# top.net
KiCad netlist of a schematic drawn in Altium Designer
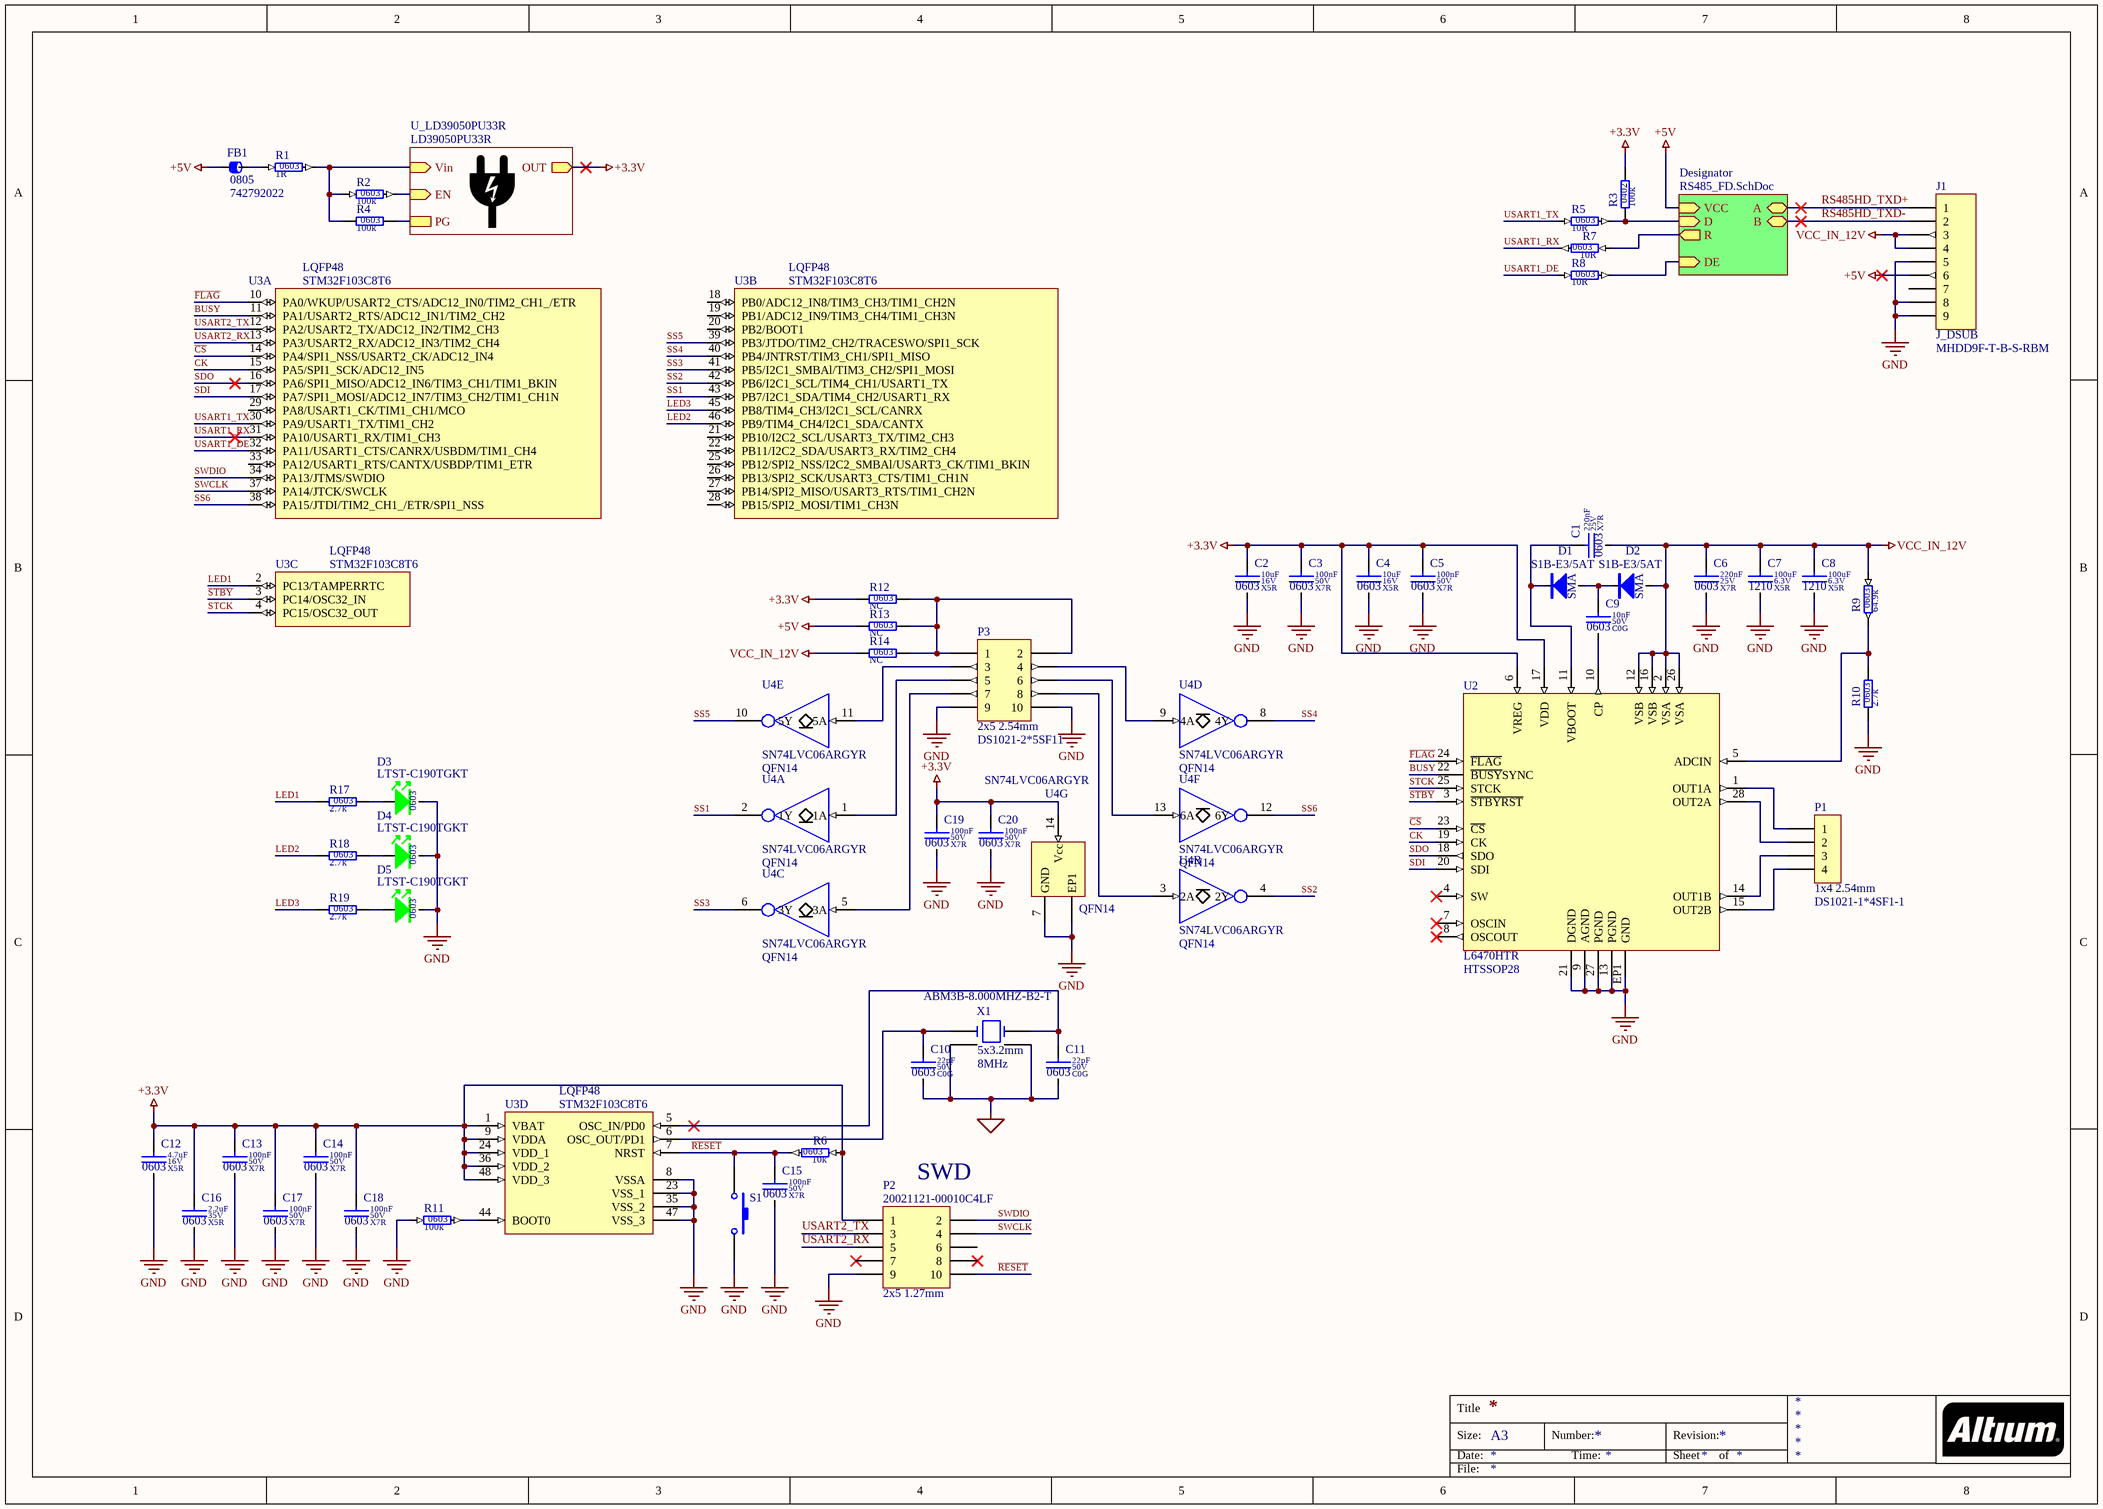
[diagram p0: top.SchDoc]

(export (version "E")
  (design (tool "Eeschema 10.0.6"))
  (components
    (comp (ref "C1")
      (value "220nF")
      (footprint "C_0603_1608")
      (description "Capacitor")
      (fields
        (field (name "DIELECTRIC") "X7R")
        (field (name "VOLTAGE") "25V")
        (field (name "SCH_FOOTPRINT") "0603")
        (field (name "PART NUMBER") "C_220nF_25V_X7R_0603_10")
        (field (name "MANUFACTURER") "Murata")
      )
      (libsource (lib "Library") (part "C"))
    )
    (comp (ref "C2")
      (value "10uF")
      (footprint "C_0603_1608")
      (description "Capacitor")
      (fields
        (field (name "DIELECTRIC") "X5R")
        (field (name "VOLTAGE") "16V")
        (field (name "SCH_FOOTPRINT") "0603")
        (field (name "PART NUMBER") "C_10uF_16V_X5R_0603_20")
        (field (name "MANUFACTURER") "Samsung Electro-Mechanics")
      )
      (libsource (lib "Library") (part "C"))
    )
    (comp (ref "C3")
      (value "100nF")
      (footprint "C_0603_1608")
      (description "Capacitor")
      (fields
        (field (name "DIELECTRIC") "X7R")
        (field (name "VOLTAGE") "50V")
        (field (name "SCH_FOOTPRINT") "0603")
        (field (name "PART NUMBER") "C_100nF_50V_X7R_0603_5")
        (field (name "MANUFACTURER") "Samsung")
      )
      (libsource (lib "Library") (part "C"))
    )
    (comp (ref "C4")
      (value "10uF")
      (footprint "C_0603_1608")
      (description "Capacitor")
      (fields
        (field (name "DIELECTRIC") "X5R")
        (field (name "VOLTAGE") "16V")
        (field (name "SCH_FOOTPRINT") "0603")
        (field (name "PART NUMBER") "C_10uF_16V_X5R_0603_20")
        (field (name "MANUFACTURER") "Samsung Electro-Mechanics")
      )
      (libsource (lib "Library") (part "C"))
    )
    (comp (ref "C5")
      (value "100nF")
      (footprint "C_0603_1608")
      (description "Capacitor")
      (fields
        (field (name "DIELECTRIC") "X7R")
        (field (name "VOLTAGE") "50V")
        (field (name "SCH_FOOTPRINT") "0603")
        (field (name "PART NUMBER") "C_100nF_50V_X7R_0603_5")
        (field (name "MANUFACTURER") "Samsung")
      )
      (libsource (lib "Library") (part "C"))
    )
    (comp (ref "C6")
      (value "220nF")
      (footprint "C_0603_1608")
      (description "Capacitor")
      (fields
        (field (name "DIELECTRIC") "X7R")
        (field (name "VOLTAGE") "25V")
        (field (name "SCH_FOOTPRINT") "0603")
        (field (name "PART NUMBER") "C_220nF_25V_X7R_0603_10")
        (field (name "MANUFACTURER") "Murata")
      )
      (libsource (lib "Library") (part "C"))
    )
    (comp (ref "C7")
      (value "100uF")
      (footprint "C_1210_3225")
      (description "Capacitor")
      (fields
        (field (name "DIELECTRIC") "X5R")
        (field (name "VOLTAGE") "6.3V")
        (field (name "SCH_FOOTPRINT") "1210")
        (field (name "PART NUMBER") "C_100uF_6.3V_X5R_1210_20")
        (field (name "MANUFACTURER") "TDK")
      )
      (libsource (lib "Library") (part "C"))
    )
    (comp (ref "C8")
      (value "100uF")
      (footprint "C_1210_3225")
      (description "Capacitor")
      (fields
        (field (name "DIELECTRIC") "X5R")
        (field (name "VOLTAGE") "6.3V")
        (field (name "SCH_FOOTPRINT") "1210")
        (field (name "PART NUMBER") "C_100uF_6.3V_X5R_1210_20")
        (field (name "MANUFACTURER") "TDK")
      )
      (libsource (lib "Library") (part "C"))
    )
    (comp (ref "C9")
      (value "10nF")
      (footprint "C_0603_1608")
      (description "Capacitor")
      (fields
        (field (name "DIELECTRIC") "C0G")
        (field (name "VOLTAGE") "50V")
        (field (name "SCH_FOOTPRINT") "0603")
        (field (name "PART NUMBER") "C_10nF_50V_C0G_0603_5")
        (field (name "MANUFACTURER") "Murata")
      )
      (libsource (lib "") (part "C_1"))
    )
    (comp (ref "C10")
      (value "22pF")
      (footprint "C_0603_1608")
      (description "Capacitor")
      (fields
        (field (name "DIELECTRIC") "C0G")
        (field (name "VOLTAGE") "50V")
        (field (name "SCH_FOOTPRINT") "0603")
        (field (name "PART NUMBER") "C_22pF_50V_C0G_0603_5")
        (field (name "MANUFACTURER") "AVX")
      )
      (libsource (lib "Library") (part "C"))
    )
    (comp (ref "C11")
      (value "22pF")
      (footprint "C_0603_1608")
      (description "Capacitor")
      (fields
        (field (name "DIELECTRIC") "C0G")
        (field (name "VOLTAGE") "50V")
        (field (name "SCH_FOOTPRINT") "0603")
        (field (name "PART NUMBER") "C_22pF_50V_C0G_0603_5")
        (field (name "MANUFACTURER") "AVX")
      )
      (libsource (lib "Library") (part "C"))
    )
    (comp (ref "C12")
      (value "4.7uF")
      (footprint "C_0603_1608")
      (description "Capacitor")
      (fields
        (field (name "DIELECTRIC") "X5R")
        (field (name "VOLTAGE") "16V")
        (field (name "SCH_FOOTPRINT") "0603")
        (field (name "PART NUMBER") "C_4.7uF_16V_X5R_0603_10")
        (field (name "MANUFACTURER") "Murata")
      )
      (libsource (lib "Library") (part "C"))
    )
    (comp (ref "C13")
      (value "100nF")
      (footprint "C_0603_1608")
      (description "Capacitor")
      (fields
        (field (name "DIELECTRIC") "X7R")
        (field (name "VOLTAGE") "50V")
        (field (name "SCH_FOOTPRINT") "0603")
        (field (name "PART NUMBER") "C_100nF_50V_X7R_0603_5")
        (field (name "MANUFACTURER") "Samsung")
      )
      (libsource (lib "Library") (part "C"))
    )
    (comp (ref "C14")
      (value "100nF")
      (footprint "C_0603_1608")
      (description "Capacitor")
      (fields
        (field (name "DIELECTRIC") "X7R")
        (field (name "VOLTAGE") "50V")
        (field (name "SCH_FOOTPRINT") "0603")
        (field (name "PART NUMBER") "C_100nF_50V_X7R_0603_5")
        (field (name "MANUFACTURER") "Samsung")
      )
      (libsource (lib "Library") (part "C"))
    )
    (comp (ref "C15")
      (value "100nF")
      (footprint "C_0603_1608")
      (description "Capacitor")
      (fields
        (field (name "DIELECTRIC") "X7R")
        (field (name "VOLTAGE") "50V")
        (field (name "SCH_FOOTPRINT") "0603")
        (field (name "PART NUMBER") "C_100nF_50V_X7R_0603_5")
        (field (name "MANUFACTURER") "Samsung")
      )
      (libsource (lib "Library") (part "C"))
    )
    (comp (ref "C16")
      (value "2.2uF")
      (footprint "C_0603_1608")
      (description "Capacitor")
      (fields
        (field (name "DIELECTRIC") "X5R")
        (field (name "VOLTAGE") "35V")
        (field (name "SCH_FOOTPRINT") "0603")
        (field (name "PART NUMBER") "C_2.2uF_35V_X5R_0603_10")
        (field (name "MANUFACTURER") "Murata")
      )
      (libsource (lib "Library") (part "C"))
    )
    (comp (ref "C17")
      (value "100nF")
      (footprint "C_0603_1608")
      (description "Capacitor")
      (fields
        (field (name "DIELECTRIC") "X7R")
        (field (name "VOLTAGE") "50V")
        (field (name "SCH_FOOTPRINT") "0603")
        (field (name "PART NUMBER") "C_100nF_50V_X7R_0603_5")
        (field (name "MANUFACTURER") "Samsung")
      )
      (libsource (lib "Library") (part "C"))
    )
    (comp (ref "C18")
      (value "100nF")
      (footprint "C_0603_1608")
      (description "Capacitor")
      (fields
        (field (name "DIELECTRIC") "X7R")
        (field (name "VOLTAGE") "50V")
        (field (name "SCH_FOOTPRINT") "0603")
        (field (name "PART NUMBER") "C_100nF_50V_X7R_0603_5")
        (field (name "MANUFACTURER") "Samsung")
      )
      (libsource (lib "Library") (part "C"))
    )
    (comp (ref "C19")
      (value "100nF")
      (footprint "C_0603_1608")
      (description "Capacitor")
      (fields
        (field (name "DIELECTRIC") "X7R")
        (field (name "VOLTAGE") "50V")
        (field (name "SCH_FOOTPRINT") "0603")
        (field (name "PART NUMBER") "C_100nF_50V_X7R_0603_5")
        (field (name "MANUFACTURER") "Samsung")
      )
      (libsource (lib "Library") (part "C"))
    )
    (comp (ref "C20")
      (value "100nF")
      (footprint "C_0603_1608")
      (description "Capacitor")
      (fields
        (field (name "DIELECTRIC") "X7R")
        (field (name "VOLTAGE") "50V")
        (field (name "SCH_FOOTPRINT") "0603")
        (field (name "PART NUMBER") "C_100nF_50V_X7R_0603_5")
        (field (name "MANUFACTURER") "Samsung")
      )
      (libsource (lib "Library") (part "C"))
    )
    (comp (ref "D1")
      (value "S1B-E3/5AT")
      (footprint "SMA_DO-214AC")
      (fields
        (field (name "SCH_FOOTPRINT") "SMA")
        (field (name "PART NUMBER") "D_S1BE3/61T_1A_100V_SMA")
        (field (name "VOLTAGE") "100V")
        (field (name "MANUFACTURER") "Vishay")
      )
      (libsource (lib "Library") (part "D"))
    )
    (comp (ref "D2")
      (value "S1B-E3/5AT")
      (footprint "SMA_DO-214AC")
      (fields
        (field (name "SCH_FOOTPRINT") "SMA")
        (field (name "PART NUMBER") "D_S1BE3/61T_1A_100V_SMA")
        (field (name "VOLTAGE") "100V")
        (field (name "MANUFACTURER") "Vishay")
      )
      (libsource (lib "Library") (part "D"))
    )
    (comp (ref "D3")
      (value "LTST-C190TGKT")
      (footprint "OL_0603_1608")
      (description "LED GREEN")
      (fields
        (field (name "SCH_FOOTPRINT") "0603")
        (field (name "PART NUMBER") "OL_G_0603")
        (field (name "MANUFACTURER") "Lite-On")
      )
      (libsource (lib "Library") (part "OL_G"))
    )
    (comp (ref "D4")
      (value "LTST-C190TGKT")
      (footprint "OL_0603_1608")
      (description "LED GREEN")
      (fields
        (field (name "SCH_FOOTPRINT") "0603")
        (field (name "PART NUMBER") "OL_G_0603")
        (field (name "MANUFACTURER") "Lite-On")
      )
      (libsource (lib "Library") (part "OL_G"))
    )
    (comp (ref "D5")
      (value "LTST-C190TGKT")
      (footprint "OL_0603_1608")
      (description "LED GREEN")
      (fields
        (field (name "SCH_FOOTPRINT") "0603")
        (field (name "PART NUMBER") "OL_G_0603")
        (field (name "MANUFACTURER") "Lite-On")
      )
      (libsource (lib "Library") (part "OL_G"))
    )
    (comp (ref "FB1")
      (value "742792022")
      (footprint "FB_0805_2012")
      (description "Ferrite Bead")
      (fields
        (field (name "PART NUMBER") "FB_742792022")
        (field (name "SCH_FOOTPRINT") "0805")
        (field (name "MANUFACTURER") "Wurth")
      )
      (libsource (lib "Library") (part "FB"))
    )
    (comp (ref "J1")
      (value "MHDD9F-T-B-S-RBM")
      (footprint "J_DSUB_MHDD9F-T-B-S-RBM")
      (description "Header, 9-Pin")
      (fields
        (field (name "SCH_FOOTPRINT") "J_DSUB")
        (field (name "PART NUMBER") "J_DSUB")
        (field (name "Comment") "DSUB 9 Pin")
      )
      (libsource (lib "Library") (part "J_DSUB"))
    )
    (comp (ref "P1")
      (value "DS1021-1*4SF1-1")
      (footprint "P_HEADER_1x4_2.54")
      (description "Pin Header")
      (fields
        (field (name "SCH_FOOTPRINT") "1x4 2.54mm")
        (field (name "PART NUMBER") "P_HEADER_1x4_2.54")
        (field (name "MANUFACTURER") "Connfly")
      )
      (libsource (lib "Library") (part "P_HEADER_1x4"))
    )
    (comp (ref "P2")
      (value "20021121-00010C4LF")
      (footprint "P_HEADER_2x5_1.27")
      (description "Header, 10-Pin, Dual row")
      (fields
        (field (name "PART NUMBER") "P_HEADER_2x5_1.27")
        (field (name "SCH_FOOTPRINT") "2x5 1.27mm")
        (field (name "MANUFACTURER") "FCI")
      )
      (libsource (lib "Library") (part "P_HEADER_2x5"))
    )
    (comp (ref "P3")
      (value "DS1021-2*5SF11")
      (footprint "P_HEADER_2x5_2.54")
      (description "Pin Header")
      (fields
        (field (name "SCH_FOOTPRINT") "2x5 2.54mm")
        (field (name "PART NUMBER") "P_HEADER_2x5_2.54")
        (field (name "MANUFACTURER") "Connfly")
      )
      (libsource (lib "") (part "P_HEADER_2x5_1"))
    )
    (comp (ref "R1")
      (value "1R")
      (footprint "R_0603_1608")
      (fields
        (field (name "SCH_FOOTPRINT") "0603")
        (field (name "PART NUMBER") "R_1R_0603_1")
        (field (name "VOLTAGE") "50V")
        (field (name "POWER") "100mW")
      )
      (libsource (lib "Library") (part "R"))
    )
    (comp (ref "R2")
      (value "100k")
      (footprint "R_0603_1608")
      (fields
        (field (name "SCH_FOOTPRINT") "0603")
        (field (name "PART NUMBER") "R_100k_0603_1")
        (field (name "VOLTAGE") "50V")
        (field (name "POWER") "100mW")
      )
      (libsource (lib "Library") (part "R"))
    )
    (comp (ref "R3")
      (value "100k")
      (footprint "R_0402_1005")
      (fields
        (field (name "SCH_FOOTPRINT") "0402")
        (field (name "PART NUMBER") "R_100k_0402_1")
        (field (name "VOLTAGE") "50V")
        (field (name "POWER") "63mW")
      )
      (libsource (lib "") (part "R_2"))
    )
    (comp (ref "R4")
      (value "100k")
      (footprint "R_0603_1608")
      (fields
        (field (name "SCH_FOOTPRINT") "0603")
        (field (name "PART NUMBER") "R_100k_0603_1")
        (field (name "VOLTAGE") "50V")
        (field (name "POWER") "100mW")
      )
      (libsource (lib "") (part "R_2"))
    )
    (comp (ref "R5")
      (value "10R")
      (footprint "R_0603_1608")
      (fields
        (field (name "SCH_FOOTPRINT") "0603")
        (field (name "PART NUMBER") "R_10R_0603_1")
        (field (name "VOLTAGE") "50V")
        (field (name "POWER") "100mW")
      )
      (libsource (lib "Library") (part "R"))
    )
    (comp (ref "R6")
      (value "10k")
      (footprint "R_0603_1608")
      (fields
        (field (name "SCH_FOOTPRINT") "0603")
        (field (name "PART NUMBER") "R_10k_0603_1")
        (field (name "VOLTAGE") "75V")
        (field (name "POWER") "100mW")
      )
      (libsource (lib "Library") (part "R"))
    )
    (comp (ref "R7")
      (value "10R")
      (footprint "R_0603_1608")
      (fields
        (field (name "SCH_FOOTPRINT") "0603")
        (field (name "PART NUMBER") "R_10R_0603_1")
        (field (name "VOLTAGE") "50V")
        (field (name "POWER") "100mW")
      )
      (libsource (lib "Library") (part "R"))
    )
    (comp (ref "R8")
      (value "10R")
      (footprint "R_0603_1608")
      (fields
        (field (name "SCH_FOOTPRINT") "0603")
        (field (name "PART NUMBER") "R_10R_0603_1")
        (field (name "VOLTAGE") "50V")
        (field (name "POWER") "100mW")
      )
      (libsource (lib "Library") (part "R"))
    )
    (comp (ref "R9")
      (value "64.9k")
      (footprint "R_0603_1608")
      (fields
        (field (name "SCH_FOOTPRINT") "0603")
        (field (name "PART NUMBER") "R_64.9k_0603_1")
        (field (name "VOLTAGE") "75V")
        (field (name "POWER") "100mW")
      )
      (libsource (lib "") (part "R_1"))
    )
    (comp (ref "R10")
      (value "2.7k")
      (footprint "R_0603_1608")
      (fields
        (field (name "SCH_FOOTPRINT") "0603")
        (field (name "PART NUMBER") "R_2.7k_0603_1")
        (field (name "VOLTAGE") "50V")
        (field (name "POWER") "100mW")
      )
      (libsource (lib "") (part "R_2"))
    )
    (comp (ref "R11")
      (value "100k")
      (footprint "R_0603_1608")
      (fields
        (field (name "SCH_FOOTPRINT") "0603")
        (field (name "PART NUMBER") "R_100k_0603_1")
        (field (name "VOLTAGE") "50V")
        (field (name "POWER") "100mW")
      )
      (libsource (lib "Library") (part "R"))
    )
    (comp (ref "R12")
      (value "NC")
      (footprint "R_NC_0603_1608")
      (fields
        (field (name "SCH_FOOTPRINT") "0603")
        (field (name "PART NUMBER") "R_GENERIC_0603")
        (field (name "Comment") "Resistor")
      )
      (libsource (lib "") (part "R_2"))
    )
    (comp (ref "R13")
      (value "NC")
      (footprint "R_NC_0603_1608")
      (fields
        (field (name "SCH_FOOTPRINT") "0603")
        (field (name "PART NUMBER") "R_GENERIC_0603")
        (field (name "Comment") "Resistor")
      )
      (libsource (lib "") (part "R_2"))
    )
    (comp (ref "R14")
      (value "NC")
      (footprint "R_NC_0603_1608")
      (fields
        (field (name "SCH_FOOTPRINT") "0603")
        (field (name "PART NUMBER") "R_GENERIC_0603")
        (field (name "Comment") "Resistor")
      )
      (libsource (lib "") (part "R_2"))
    )
    (comp (ref "R17")
      (value "2.7k")
      (footprint "R_0603_1608")
      (fields
        (field (name "SCH_FOOTPRINT") "0603")
        (field (name "PART NUMBER") "R_2.7k_0603_1")
        (field (name "VOLTAGE") "50V")
        (field (name "POWER") "100mW")
      )
      (libsource (lib "") (part "R_2"))
    )
    (comp (ref "R18")
      (value "2.7k")
      (footprint "R_0603_1608")
      (fields
        (field (name "SCH_FOOTPRINT") "0603")
        (field (name "PART NUMBER") "R_2.7k_0603_1")
        (field (name "VOLTAGE") "50V")
        (field (name "POWER") "100mW")
      )
      (libsource (lib "") (part "R_2"))
    )
    (comp (ref "R19")
      (value "2.7k")
      (footprint "R_0603_1608")
      (fields
        (field (name "SCH_FOOTPRINT") "0603")
        (field (name "PART NUMBER") "R_2.7k_0603_1")
        (field (name "VOLTAGE") "50V")
        (field (name "POWER") "100mW")
      )
      (libsource (lib "") (part "R_2"))
    )
    (comp (ref "S1")
      (value "3x6mm")
      (footprint "S_TACTSWITCH3x6")
      (description "Tact Switch")
      (fields (field (name "PART NUMBER") "S_TACTSWITCH") (field (name "MANUFACTURER") "Ninigi"))
      (libsource (lib "Library") (part "S_TACTSWITCH"))
    )
    (comp (ref "U2")
      (value "L6470HTR")
      (footprint "HTSSOP28")
      (fields
        (field (name "SCH_FOOTPRINT") "HTSSOP28")
        (field (name "PART NUMBER") "U_L6470HTR")
        (field (name "MANUFACTURER") "STMicroelectronics")
        (field (name "Comment") "Fully integrated microstepping motor driver with motion engine and SPI")
      )
      (libsource (lib "Library") (part "U_L6470"))
    )
    (comp (ref "U3")
      (value "STM32F103C8T6")
      (footprint "LQFP48_7x7")
      (fields
        (field (name "SCH_FOOTPRINT") "LQFP48")
        (field (name "PART NUMBER") "UP_STM32F103C8T6")
        (field (name "MANUFACTURER") "STMicroelectronics")
      )
      (libsource (lib "Library") (part "UP_STM32F103Cx"))
    )
    (comp (ref "U4")
      (value "SN74LVC06ARGYR")
      (footprint "QFN14_4x4")
      (fields
        (field (name "PART NUMBER") "U_SN74LVC06ARGYR")
        (field (name "SCH_FOOTPRINT") "QFN14")
        (field (name "MANUFACTURER") "Texas Instruments")
        (field (name "Comment") "Open drain buffer")
      )
      (libsource (lib "") (part "U_SN74LVC06A_3"))
    )
    (comp (ref "X1")
      (value "8MHz")
      (footprint "X_ABM3B_5X3X11")
      (fields
        (field (name "PART NUMBER") "X_ABM3B-8.000MHZ-B2-T")
        (field (name "MANUFACTURER PART NUMBER") "ABM3B-8.000MHZ-B2-T")
        (field (name "SCH_FOOTPRINT") "5x3.2mm")
        (field (name "MANUFACTURER") "Abracon")
      )
      (libsource (lib "Library") (part "X_ABM3B"))
    )
  )
  (nets
    (net (code "1") (name "+3.3V") (class "Default")
      (node (ref "C12") (pin "1") (pinfunction "1_1") (pintype "passive"))
      (node (ref "C13") (pin "1") (pinfunction "1_1") (pintype "passive"))
      (node (ref "C14") (pin "1") (pinfunction "1_1") (pintype "passive"))
      (node (ref "C16") (pin "1") (pinfunction "1_1") (pintype "passive"))
      (node (ref "C17") (pin "1") (pinfunction "1_1") (pintype "passive"))
      (node (ref "C18") (pin "1") (pinfunction "1_1") (pintype "passive"))
      (node (ref "C19") (pin "1") (pinfunction "1_1") (pintype "passive"))
      (node (ref "C2") (pin "1") (pinfunction "1_1") (pintype "passive"))
      (node (ref "C20") (pin "1") (pinfunction "1_1") (pintype "passive"))
      (node (ref "C3") (pin "1") (pinfunction "1_1") (pintype "passive"))
      (node (ref "C4") (pin "1") (pinfunction "1_1") (pintype "passive"))
      (node (ref "C5") (pin "1") (pinfunction "1_1") (pintype "passive"))
      (node (ref "P2") (pin "1") (pinfunction "1_1") (pintype "passive"))
      (node (ref "R12") (pin "1") (pinfunction "1_1") (pintype "passive"))
      (node (ref "R3") (pin "2") (pinfunction "2_2") (pintype "passive"))
      (node (ref "R6") (pin "1") (pinfunction "1_1") (pintype "input"))
      (node (ref "U2") (pin "17") (pinfunction "VDD_17") (pintype "input"))
      (node (ref "U2") (pin "6") (pinfunction "VREG_6") (pintype "input"))
      (node (ref "U3") (pin "1") (pinfunction "VBAT_1") (pintype "input"))
      (node (ref "U3") (pin "24") (pinfunction "VDD_1_24") (pintype "input"))
      (node (ref "U3") (pin "36") (pinfunction "VDD_2_36") (pintype "input"))
      (node (ref "U3") (pin "48") (pinfunction "VDD_3_48") (pintype "input"))
      (node (ref "U3") (pin "9") (pinfunction "VDDA_9") (pintype "input"))
      (node (ref "U4") (pin "14") (pinfunction "Vcc_14") (pintype "input"))
    )
    (net (code "2") (name "+5V") (class "Default")
      (node (ref "FB1") (pin "1") (pintype "input"))
      (node (ref "J1") (pin "6") (pinfunction "6_6") (pintype "output"))
      (node (ref "R13") (pin "1") (pinfunction "1_1") (pintype "passive"))
    )
    (net (code "3") (name "/BUSY") (class "Default")
      (node (ref "U2") (pin "22") (pinfunction "~{BUSY}SYNC_22") (pintype "open_collector"))
      (node (ref "U3") (pin "11") (pinfunction "PA1/USART2_RTS/ADC12_IN1/TIM2_CH2_11") (pintype "bidirectional"))
    )
    (net (code "4") (name "/CK") (class "Default")
      (node (ref "U2") (pin "19") (pinfunction "CK_19") (pintype "input"))
      (node (ref "U3") (pin "15") (pinfunction "PA5/SPI1_SCK/ADC12_IN5_15") (pintype "bidirectional"))
    )
    (net (code "5") (name "/D") (class "Default")
      (node (ref "R3") (pin "1") (pinfunction "1_1") (pintype "passive"))
      (node (ref "R5") (pin "2") (pinfunction "2_2") (pintype "output"))
    )
    (net (code "6") (name "/DE") (class "Default")
      (node (ref "R8") (pin "2") (pinfunction "2_2") (pintype "output"))
    )
    (net (code "7") (name "/EN") (class "Default")
      (node (ref "R2") (pin "2") (pinfunction "2_2") (pintype "output"))
    )
    (net (code "8") (name "/LED1") (class "Default")
      (node (ref "R17") (pin "1") (pinfunction "1_1") (pintype "passive"))
      (node (ref "U3") (pin "2") (pinfunction "PC13/TAMPERRTC_2") (pintype "bidirectional"))
    )
    (net (code "9") (name "/LED2") (class "Default")
      (node (ref "R18") (pin "1") (pinfunction "1_1") (pintype "passive"))
      (node (ref "U3") (pin "46") (pinfunction "PB9/TIM4_CH4/I2C1_SDA/CANTX_46") (pintype "bidirectional"))
    )
    (net (code "10") (name "/LED3") (class "Default")
      (node (ref "R19") (pin "1") (pinfunction "1_1") (pintype "passive"))
      (node (ref "U3") (pin "45") (pinfunction "PB8/TIM4_CH3/I2C1_SCL/CANRX_45") (pintype "bidirectional"))
    )
    (net (code "11") (name "/PG") (class "Default")
      (node (ref "R4") (pin "2") (pinfunction "2_2") (pintype "passive"))
    )
    (net (code "12") (name "/R") (class "Default")
      (node (ref "R7") (pin "1") (pinfunction "1_1") (pintype "input"))
    )
    (net (code "13") (name "/RS485HD_TXD+") (class "Default")
      (node (ref "J1") (pin "1") (pinfunction "1_1") (pintype "passive"))
    )
    (net (code "14") (name "/RS485HD_TXD-") (class "Default")
      (node (ref "J1") (pin "2") (pinfunction "2_2") (pintype "passive"))
    )
    (net (code "15") (name "/SDI") (class "Default")
      (node (ref "U2") (pin "20") (pinfunction "SDI_20") (pintype "input"))
      (node (ref "U3") (pin "17") (pinfunction "PA7/SPI1_MOSI/ADC12_IN7/TIM3_CH2/TIM1_CH1N_17") (pintype "bidirectional"))
    )
    (net (code "16") (name "/SDO") (class "Default")
      (node (ref "U2") (pin "18") (pinfunction "SDO_18") (pintype "output"))
      (node (ref "U3") (pin "16") (pinfunction "PA6/SPI1_MISO/ADC12_IN6/TIM3_CH1/TIM1_BKIN_16") (pintype "bidirectional"))
    )
    (net (code "17") (name "/SS1") (class "Default")
      (node (ref "U3") (pin "43") (pinfunction "PB7/I2C1_SDA/TIM4_CH2/USART1_RX_43") (pintype "bidirectional"))
      (node (ref "U4") (pin "2") (pinfunction "1Y_2") (pintype "open_collector"))
    )
    (net (code "18") (name "/SS2") (class "Default")
      (node (ref "U3") (pin "42") (pinfunction "PB6/I2C1_SCL/TIM4_CH1/USART1_TX_42") (pintype "bidirectional"))
      (node (ref "U4") (pin "4") (pinfunction "2Y_4") (pintype "open_collector"))
    )
    (net (code "19") (name "/SS3") (class "Default")
      (node (ref "U3") (pin "41") (pinfunction "PB5/I2C1_SMBAl/TIM3_CH2/SPI1_MOSI_41") (pintype "bidirectional"))
      (node (ref "U4") (pin "6") (pinfunction "3Y_6") (pintype "open_collector"))
    )
    (net (code "20") (name "/SS4") (class "Default")
      (node (ref "U3") (pin "40") (pinfunction "PB4/JNTRST/TIM3_CH1/SPI1_MISO_40") (pintype "bidirectional"))
      (node (ref "U4") (pin "8") (pinfunction "4Y_8") (pintype "open_collector"))
    )
    (net (code "21") (name "/SS5") (class "Default")
      (node (ref "U3") (pin "39") (pinfunction "PB3/JTDO/TIM2_CH2/TRACESWO/SPI1_SCK_39") (pintype "bidirectional"))
      (node (ref "U4") (pin "10") (pinfunction "5Y_10") (pintype "open_collector"))
    )
    (net (code "22") (name "/SS6") (class "Default")
      (node (ref "U3") (pin "38") (pinfunction "PA15/JTDI/TIM2_CH1_/ETR/SPI1_NSS_38") (pintype "bidirectional"))
      (node (ref "U4") (pin "12") (pinfunction "6Y_12") (pintype "open_collector"))
    )
    (net (code "23") (name "/STCK") (class "Default")
      (node (ref "U2") (pin "25") (pinfunction "STCK_25") (pintype "input"))
      (node (ref "U3") (pin "4") (pinfunction "PC15/OSC32_OUT_4") (pintype "bidirectional"))
    )
    (net (code "24") (name "/SWCLK") (class "Default")
      (node (ref "P2") (pin "4") (pinfunction "4_4") (pintype "passive"))
      (node (ref "U3") (pin "37") (pinfunction "PA14/JTCK/SWCLK_37") (pintype "bidirectional"))
    )
    (net (code "25") (name "/SWDIO") (class "Default")
      (node (ref "P2") (pin "2") (pinfunction "2_2") (pintype "passive"))
      (node (ref "U3") (pin "34") (pinfunction "PA13/JTMS/SWDIO_34") (pintype "bidirectional"))
    )
    (net (code "26") (name "/USART1_DE") (class "Default")
      (node (ref "R8") (pin "1") (pinfunction "1_1") (pintype "input"))
      (node (ref "U3") (pin "32") (pinfunction "PA11/USART1_CTS/CANRX/USBDM/TIM1_CH4_32") (pintype "bidirectional"))
    )
    (net (code "27") (name "/USART1_RX") (class "Default")
      (node (ref "R7") (pin "2") (pinfunction "2_2") (pintype "output"))
      (node (ref "U3") (pin "31") (pinfunction "PA10/USART1_RX/TIM1_CH3_31") (pintype "bidirectional"))
    )
    (net (code "28") (name "/USART1_TX") (class "Default")
      (node (ref "R5") (pin "1") (pinfunction "1_1") (pintype "input"))
      (node (ref "U3") (pin "30") (pinfunction "PA9/USART1_TX/TIM1_CH2_30") (pintype "bidirectional"))
    )
    (net (code "29") (name "/USART2_RX") (class "Default")
      (node (ref "P2") (pin "5") (pinfunction "5_5") (pintype "passive"))
      (node (ref "U3") (pin "13") (pinfunction "PA3/USART2_RX/ADC12_IN3/TIM2_CH4_13") (pintype "bidirectional"))
    )
    (net (code "30") (name "/USART2_TX") (class "Default")
      (node (ref "P2") (pin "3") (pinfunction "3_3") (pintype "passive"))
      (node (ref "U3") (pin "12") (pinfunction "PA2/USART2_TX/ADC12_IN2/TIM2_CH3_12") (pintype "bidirectional"))
    )
    (net (code "31") (name "/Vin") (class "Default")
      (node (ref "R1") (pin "2") (pinfunction "2_2") (pintype "output"))
      (node (ref "R2") (pin "1") (pinfunction "1_1") (pintype "input"))
      (node (ref "R4") (pin "1") (pinfunction "1_1") (pintype "passive"))
    )
    (net (code "32") (name "/~{CS}") (class "Default")
      (node (ref "U2") (pin "23") (pinfunction "~{CS}_23") (pintype "input"))
      (node (ref "U3") (pin "14") (pinfunction "PA4/SPI1_NSS/USART2_CK/ADC12_IN4_14") (pintype "bidirectional"))
    )
    (net (code "33") (name "/~{FLAG}") (class "Default")
      (node (ref "U2") (pin "24") (pinfunction "~{FLAG}_24") (pintype "input"))
      (node (ref "U3") (pin "10") (pinfunction "PA0/WKUP/USART2_CTS/ADC12_IN0/TIM2_CH1_/ETR_10") (pintype "bidirectional"))
    )
    (net (code "34") (name "/~{RESET}") (class "Default")
      (node (ref "C15") (pin "1") (pinfunction "1_1") (pintype "passive"))
      (node (ref "P2") (pin "10") (pinfunction "10_10") (pintype "passive"))
      (node (ref "R6") (pin "2") (pinfunction "2_2") (pintype "output"))
      (node (ref "S1") (pin "1") (pinfunction "1_1") (pintype "passive"))
      (node (ref "U3") (pin "7") (pinfunction "NRST_7") (pintype "input"))
    )
    (net (code "35") (name "/~{STBY}") (class "Default")
      (node (ref "U2") (pin "3") (pinfunction "~{STBYRST}_3") (pintype "input"))
      (node (ref "U3") (pin "3") (pinfunction "PC14/OSC32_IN_3") (pintype "bidirectional"))
    )
    (net (code "36") (name "GND") (class "Default")
      (node (ref "C10") (pin "2") (pinfunction "2_2") (pintype "passive"))
      (node (ref "C11") (pin "2") (pinfunction "2_2") (pintype "passive"))
      (node (ref "C12") (pin "2") (pinfunction "2_2") (pintype "passive"))
      (node (ref "C13") (pin "2") (pinfunction "2_2") (pintype "passive"))
      (node (ref "C14") (pin "2") (pinfunction "2_2") (pintype "passive"))
      (node (ref "C15") (pin "2") (pinfunction "2_2") (pintype "passive"))
      (node (ref "C16") (pin "2") (pinfunction "2_2") (pintype "passive"))
      (node (ref "C17") (pin "2") (pinfunction "2_2") (pintype "passive"))
      (node (ref "C18") (pin "2") (pinfunction "2_2") (pintype "passive"))
      (node (ref "C19") (pin "2") (pinfunction "2_2") (pintype "passive"))
      (node (ref "C2") (pin "2") (pinfunction "2_2") (pintype "passive"))
      (node (ref "C20") (pin "2") (pinfunction "2_2") (pintype "passive"))
      (node (ref "C3") (pin "2") (pinfunction "2_2") (pintype "passive"))
      (node (ref "C4") (pin "2") (pinfunction "2_2") (pintype "passive"))
      (node (ref "C5") (pin "2") (pinfunction "2_2") (pintype "passive"))
      (node (ref "C6") (pin "2") (pinfunction "2_2") (pintype "passive"))
      (node (ref "C7") (pin "2") (pinfunction "2_2") (pintype "passive"))
      (node (ref "C8") (pin "2") (pinfunction "2_2") (pintype "passive"))
      (node (ref "D3") (pin "1") (pinfunction "K_1") (pintype "passive"))
      (node (ref "D4") (pin "1") (pinfunction "K_1") (pintype "passive"))
      (node (ref "D5") (pin "1") (pinfunction "K_1") (pintype "passive"))
      (node (ref "J1") (pin "5") (pinfunction "5_5") (pintype "passive"))
      (node (ref "J1") (pin "8") (pinfunction "8_8") (pintype "passive"))
      (node (ref "J1") (pin "9") (pinfunction "9_9") (pintype "passive"))
      (node (ref "P2") (pin "9") (pinfunction "9_9") (pintype "passive"))
      (node (ref "P3") (pin "10") (pinfunction "10_10") (pintype "passive"))
      (node (ref "P3") (pin "9") (pinfunction "9_9") (pintype "passive"))
      (node (ref "R10") (pin "1") (pinfunction "1_1") (pintype "passive"))
      (node (ref "R11") (pin "1") (pinfunction "1_1") (pintype "input"))
      (node (ref "S1") (pin "2") (pinfunction "2_2") (pintype "passive"))
      (node (ref "U2") (pin "13") (pinfunction "PGND_13") (pintype "power_in"))
      (node (ref "U2") (pin "21") (pinfunction "DGND_21") (pintype "power_in"))
      (node (ref "U2") (pin "27") (pinfunction "PGND_27") (pintype "power_in"))
      (node (ref "U2") (pin "9") (pinfunction "AGND_9") (pintype "power_in"))
      (node (ref "U2") (pin "EP1") (pinfunction "GND_EP1") (pintype "power_in"))
      (node (ref "U3") (pin "23") (pinfunction "VSS_1_23") (pintype "power_in"))
      (node (ref "U3") (pin "35") (pinfunction "VSS_2_35") (pintype "power_in"))
      (node (ref "U3") (pin "47") (pinfunction "VSS_3_47") (pintype "power_in"))
      (node (ref "U3") (pin "8") (pinfunction "VSSA_8") (pintype "power_in"))
      (node (ref "U4") (pin "7") (pinfunction "GND_7") (pintype "power_in"))
      (node (ref "U4") (pin "EP1") (pinfunction "EP1_EP1") (pintype "power_in"))
      (node (ref "X1") (pin "2") (pinfunction "GND_2") (pintype "power_in"))
      (node (ref "X1") (pin "4") (pinfunction "GND_4") (pintype "power_in"))
    )
    (net (code "37") (name "Net-(C9-Pad1)") (class "Default")
      (node (ref "C9") (pin "1") (pinfunction "1_1") (pintype "output"))
      (node (ref "D1") (pin "2") (pintype "input"))
      (node (ref "D2") (pin "1") (pintype "output"))
    )
    (net (code "38") (name "Net-(D3-A)") (class "Default")
      (node (ref "D3") (pin "2") (pinfunction "A_2") (pintype "passive"))
      (node (ref "R17") (pin "2") (pinfunction "2_2") (pintype "passive"))
    )
    (net (code "39") (name "Net-(D4-A)") (class "Default")
      (node (ref "D4") (pin "2") (pinfunction "A_2") (pintype "passive"))
      (node (ref "R18") (pin "2") (pinfunction "2_2") (pintype "passive"))
    )
    (net (code "40") (name "Net-(D5-A)") (class "Default")
      (node (ref "D5") (pin "2") (pinfunction "A_2") (pintype "passive"))
      (node (ref "R19") (pin "2") (pinfunction "2_2") (pintype "passive"))
    )
    (net (code "41") (name "Net-(FB1-Pad2)") (class "Default")
      (node (ref "FB1") (pin "2") (pintype "output"))
      (node (ref "R1") (pin "1") (pinfunction "1_1") (pintype "input"))
    )
    (net (code "42") (name "Net-(P3-Pad1)") (class "Default")
      (node (ref "P3") (pin "1") (pinfunction "1_1") (pintype "passive"))
      (node (ref "P3") (pin "2") (pinfunction "2_2") (pintype "passive"))
      (node (ref "R12") (pin "2") (pinfunction "2_2") (pintype "passive"))
      (node (ref "R13") (pin "2") (pinfunction "2_2") (pintype "passive"))
      (node (ref "R14") (pin "2") (pinfunction "2_2") (pintype "passive"))
    )
    (net (code "43") (name "Net-(U2-ADCIN)") (class "Default")
      (node (ref "R10") (pin "2") (pinfunction "2_2") (pintype "passive"))
      (node (ref "R9") (pin "1") (pinfunction "1_1") (pintype "output"))
      (node (ref "U2") (pin "5") (pinfunction "ADCIN_5") (pintype "input"))
    )
    (net (code "44") (name "Net-(U2-CP)") (class "Default")
      (node (ref "C9") (pin "2") (pinfunction "2_2") (pintype "input"))
      (node (ref "U2") (pin "10") (pinfunction "CP_10") (pintype "output"))
    )
    (net (code "45") (name "Net-(U2-OUT1A)") (class "Default")
      (node (ref "P1") (pin "1") (pinfunction "1_1") (pintype "passive"))
      (node (ref "U2") (pin "1") (pinfunction "OUT1A_1") (pintype "output"))
    )
    (net (code "46") (name "Net-(U2-OUT1B)") (class "Default")
      (node (ref "P1") (pin "3") (pinfunction "3_3") (pintype "passive"))
      (node (ref "U2") (pin "14") (pinfunction "OUT1B_14") (pintype "output"))
    )
    (net (code "47") (name "Net-(U2-OUT2A)") (class "Default")
      (node (ref "P1") (pin "2") (pinfunction "2_2") (pintype "passive"))
      (node (ref "U2") (pin "28") (pinfunction "OUT2A_28") (pintype "output"))
    )
    (net (code "48") (name "Net-(U2-OUT2B)") (class "Default")
      (node (ref "P1") (pin "4") (pinfunction "4_4") (pintype "passive"))
      (node (ref "U2") (pin "15") (pinfunction "OUT2B_15") (pintype "output"))
    )
    (net (code "49") (name "Net-(U2-VBOOT)") (class "Default")
      (node (ref "C1") (pin "1") (pinfunction "1_1") (pintype "passive"))
      (node (ref "D1") (pin "1") (pintype "output"))
      (node (ref "U2") (pin "11") (pinfunction "VBOOT_11") (pintype "input"))
    )
    (net (code "50") (name "Net-(U3D-BOOT0)") (class "Default")
      (node (ref "R11") (pin "2") (pinfunction "2_2") (pintype "output"))
      (node (ref "U3") (pin "44") (pinfunction "BOOT0_44") (pintype "input"))
    )
    (net (code "51") (name "Net-(U3D-OSC_IN{slash}PD0)") (class "Default")
      (node (ref "C11") (pin "1") (pinfunction "1_1") (pintype "passive"))
      (node (ref "U3") (pin "5") (pinfunction "OSC_IN/PD0_5") (pintype "input"))
      (node (ref "X1") (pin "1") (pinfunction "1_1") (pintype "passive"))
    )
    (net (code "52") (name "Net-(U3D-OSC_OUT{slash}PD1)") (class "Default")
      (node (ref "C10") (pin "1") (pinfunction "1_1") (pintype "passive"))
      (node (ref "U3") (pin "6") (pinfunction "OSC_OUT/PD1_6") (pintype "output"))
      (node (ref "X1") (pin "3") (pinfunction "3_3") (pintype "passive"))
    )
    (net (code "53") (name "Net-(U4A-1A)") (class "Default")
      (node (ref "P3") (pin "5") (pinfunction "5_5") (pintype "output"))
      (node (ref "U4") (pin "1") (pinfunction "1A_1") (pintype "input"))
    )
    (net (code "54") (name "Net-(U4B-2A)") (class "Default")
      (node (ref "P3") (pin "8") (pinfunction "8_8") (pintype "output"))
      (node (ref "U4") (pin "3") (pinfunction "2A_3") (pintype "input"))
    )
    (net (code "55") (name "Net-(U4C-3A)") (class "Default")
      (node (ref "P3") (pin "7") (pinfunction "7_7") (pintype "output"))
      (node (ref "U4") (pin "5") (pinfunction "3A_5") (pintype "input"))
    )
    (net (code "56") (name "Net-(U4D-4A)") (class "Default")
      (node (ref "P3") (pin "4") (pinfunction "4_4") (pintype "output"))
      (node (ref "U4") (pin "9") (pinfunction "4A_9") (pintype "input"))
    )
    (net (code "57") (name "Net-(U4E-5A)") (class "Default")
      (node (ref "P3") (pin "3") (pinfunction "3_3") (pintype "output"))
      (node (ref "U4") (pin "11") (pinfunction "5A_11") (pintype "input"))
    )
    (net (code "58") (name "Net-(U4F-6A)") (class "Default")
      (node (ref "P3") (pin "6") (pinfunction "6_6") (pintype "output"))
      (node (ref "U4") (pin "13") (pinfunction "6A_13") (pintype "input"))
    )
    (net (code "59") (name "VCC_IN_12V") (class "Default")
      (node (ref "C1") (pin "2") (pinfunction "2_2") (pintype "passive"))
      (node (ref "C6") (pin "1") (pinfunction "1_1") (pintype "passive"))
      (node (ref "C7") (pin "1") (pinfunction "1_1") (pintype "passive"))
      (node (ref "C8") (pin "1") (pinfunction "1_1") (pintype "passive"))
      (node (ref "D2") (pin "2") (pintype "input"))
      (node (ref "J1") (pin "3") (pinfunction "3_3") (pintype "output"))
      (node (ref "J1") (pin "4") (pinfunction "4_4") (pintype "passive"))
      (node (ref "R14") (pin "1") (pinfunction "1_1") (pintype "passive"))
      (node (ref "R9") (pin "2") (pinfunction "2_2") (pintype "input"))
      (node (ref "U2") (pin "12") (pinfunction "VSB_12") (pintype "input"))
      (node (ref "U2") (pin "16") (pinfunction "VSB_16") (pintype "input"))
      (node (ref "U2") (pin "2") (pinfunction "VSA_2") (pintype "input"))
      (node (ref "U2") (pin "26") (pinfunction "VSA_26") (pintype "input"))
    )
    (net (code "60") (name "unconnected-(J1-NC-Pad0)") (class "Default")
      (node (ref "J1") (pin "0") (pinfunction "NC_0") (pintype "passive"))
    )
    (net (code "61") (name "unconnected-(J1-Pad7)") (class "Default")
      (node (ref "J1") (pin "7") (pinfunction "7_7") (pintype "passive"))
    )
    (net (code "62") (name "unconnected-(P2-Pad6)") (class "Default")
      (node (ref "P2") (pin "6") (pinfunction "6_6") (pintype "passive"))
    )
    (net (code "63") (name "unconnected-(P2-Pad7)") (class "Default")
      (node (ref "P2") (pin "7") (pinfunction "7_7") (pintype "passive+no_connect"))
    )
    (net (code "64") (name "unconnected-(P2-Pad8)") (class "Default")
      (node (ref "P2") (pin "8") (pinfunction "8_8") (pintype "passive+no_connect"))
    )
    (net (code "65") (name "unconnected-(U2-OSCIN-Pad7)") (class "Default")
      (node (ref "U2") (pin "7") (pinfunction "OSCIN_7") (pintype "input+no_connect"))
    )
    (net (code "66") (name "unconnected-(U2-OSCOUT-Pad8)") (class "Default")
      (node (ref "U2") (pin "8") (pinfunction "OSCOUT_8") (pintype "output+no_connect"))
    )
    (net (code "67") (name "unconnected-(U2-SW-Pad4)") (class "Default")
      (node (ref "U2") (pin "4") (pinfunction "SW_4") (pintype "input+no_connect"))
    )
    (net (code "68") (name "unconnected-(U3A-PA8{slash}USART1_CK{slash}TIM1_CH1{slash}MCO-Pad29)") (class "Default")
      (node (ref "U3") (pin "29") (pinfunction "PA8/USART1_CK/TIM1_CH1/MCO_29") (pintype "bidirectional"))
    )
    (net (code "69") (name "unconnected-(U3A-PA12{slash}USART1_RTS{slash}CANTX{slash}USBDP{slash}TIM1_ETR-Pad33)") (class "Default")
      (node (ref "U3") (pin "33") (pinfunction "PA12/USART1_RTS/CANTX/USBDP/TIM1_ETR_33") (pintype "bidirectional"))
    )
    (net (code "70") (name "unconnected-(U3B-PB0{slash}ADC12_IN8{slash}TIM3_CH3{slash}TIM1_CH2N-Pad18)") (class "Default")
      (node (ref "U3") (pin "18") (pinfunction "PB0/ADC12_IN8/TIM3_CH3/TIM1_CH2N_18") (pintype "bidirectional"))
    )
    (net (code "71") (name "unconnected-(U3B-PB1{slash}ADC12_IN9{slash}TIM3_CH4{slash}TIM1_CH3N-Pad19)") (class "Default")
      (node (ref "U3") (pin "19") (pinfunction "PB1/ADC12_IN9/TIM3_CH4/TIM1_CH3N_19") (pintype "bidirectional"))
    )
    (net (code "72") (name "unconnected-(U3B-PB2{slash}BOOT1-Pad20)") (class "Default")
      (node (ref "U3") (pin "20") (pinfunction "PB2/BOOT1_20") (pintype "bidirectional"))
    )
    (net (code "73") (name "unconnected-(U3B-PB10{slash}I2C2_SCL{slash}USART3_TX{slash}TIM2_CH3-Pad21)") (class "Default")
      (node (ref "U3") (pin "21") (pinfunction "PB10/I2C2_SCL/USART3_TX/TIM2_CH3_21") (pintype "bidirectional"))
    )
    (net (code "74") (name "unconnected-(U3B-PB11{slash}I2C2_SDA{slash}USART3_RX{slash}TIM2_CH4-Pad22)") (class "Default")
      (node (ref "U3") (pin "22") (pinfunction "PB11/I2C2_SDA/USART3_RX/TIM2_CH4_22") (pintype "bidirectional"))
    )
    (net (code "75") (name "unconnected-(U3B-PB12{slash}SPI2_NSS{slash}I2C2_SMBAl{slash}USART3_CK{slash}TIM1_BKIN-Pad25)") (class "Default")
      (node (ref "U3") (pin "25") (pinfunction "PB12/SPI2_NSS/I2C2_SMBAl/USART3_CK/TIM1_BKIN_25") (pintype "bidirectional"))
    )
    (net (code "76") (name "unconnected-(U3B-PB13{slash}SPI2_SCK{slash}USART3_CTS{slash}TIM1_CH1N-Pad26)") (class "Default")
      (node (ref "U3") (pin "26") (pinfunction "PB13/SPI2_SCK/USART3_CTS/TIM1_CH1N_26") (pintype "bidirectional"))
    )
    (net (code "77") (name "unconnected-(U3B-PB14{slash}SPI2_MISO{slash}USART3_RTS{slash}TIM1_CH2N-Pad27)") (class "Default")
      (node (ref "U3") (pin "27") (pinfunction "PB14/SPI2_MISO/USART3_RTS/TIM1_CH2N_27") (pintype "bidirectional"))
    )
    (net (code "78") (name "unconnected-(U3B-PB15{slash}SPI2_MOSI{slash}TIM1_CH3N-Pad28)") (class "Default")
      (node (ref "U3") (pin "28") (pinfunction "PB15/SPI2_MOSI/TIM1_CH3N_28") (pintype "bidirectional"))
    )
  )
)
